# HC-05.net
KiCad netlist of a schematic drawn in Altium Designer
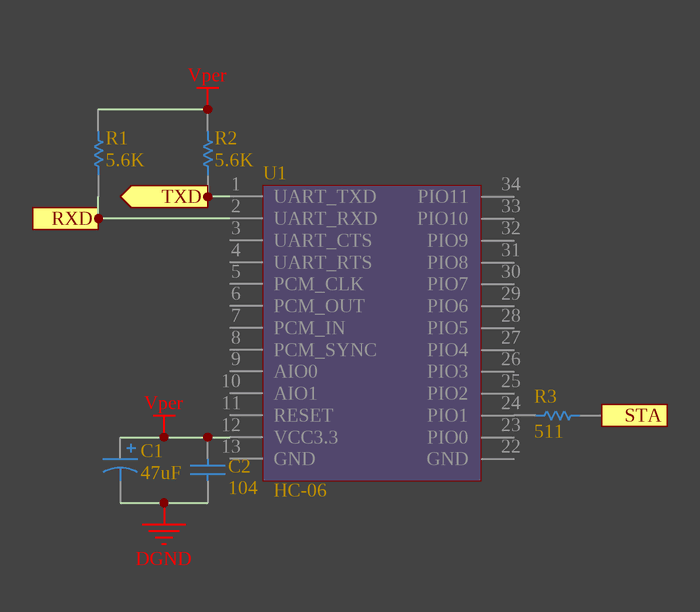
[diagram p0: HC-05.SchDoc]

(export (version "E")
  (design (tool "Eeschema 10.0.6"))
  (components
    (comp (ref "C1")
      (value "47uF")
      (footprint "贴片电解 6.3*5.4")
      (description "Polarized Capacitor (Axial)")
      (fields (field (name "PUBLISHER") "Altium Limited"))
      (libsource (lib "iMag") (part "电解电容"))
    )
    (comp (ref "C2")
      (value "104")
      (footprint "C0402")
      (description "Capacitor")
      (fields (field (name "PUBLISHER") "Altium Limited"))
      (libsource (lib "iMag") (part "电容"))
    )
    (comp (ref "R1")
      (value "5.6K")
      (footprint "R0402")
      (description "Resistor")
      (fields (field (name "PUBLISHER") "Altium Limited"))
      (libsource (lib "iMag") (part "电阻"))
    )
    (comp (ref "R2")
      (value "5.6K")
      (footprint "R0402")
      (description "Resistor")
      (fields (field (name "PUBLISHER") "Altium Limited"))
      (libsource (lib "iMag") (part "电阻"))
    )
    (comp (ref "R3")
      (value "511")
      (footprint "R0402")
      (description "Resistor")
      (fields (field (name "PUBLISHER") "Altium Limited"))
      (libsource (lib "iMag") (part "电阻"))
    )
    (comp (ref "U1")
      (value "HC-06")
      (footprint "HC-05")
      (description "蓝牙串口模块")
      (libsource (lib "iMag") (part "HC-05"))
    )
  )
  (nets
    (net (code "1") (name "/RXD") (class "Default")
      (node (ref "R1") (pin "1") (pinfunction "1_1") (pintype "passive"))
      (node (ref "U1") (pin "2") (pinfunction "UART_RXD_2") (pintype "passive"))
    )
    (net (code "2") (name "/STA") (class "Default")
      (node (ref "R3") (pin "1") (pinfunction "1_1") (pintype "passive"))
    )
    (net (code "3") (name "/TXD") (class "Default")
      (node (ref "R2") (pin "1") (pinfunction "1_1") (pintype "passive"))
      (node (ref "U1") (pin "1") (pinfunction "UART_TXD_1") (pintype "passive"))
    )
    (net (code "4") (name "DGND") (class "Default")
      (node (ref "C1") (pin "2") (pinfunction "2_2") (pintype "passive"))
      (node (ref "C2") (pin "1") (pinfunction "1_1") (pintype "passive"))
    )
    (net (code "5") (name "Net-(U1-PIO1)") (class "Default")
      (node (ref "R3") (pin "2") (pinfunction "2_2") (pintype "passive"))
      (node (ref "U1") (pin "24") (pinfunction "PIO1_24") (pintype "passive"))
    )
    (net (code "6") (name "Vper") (class "Default")
      (node (ref "C1") (pin "1") (pinfunction "1_1") (pintype "passive"))
      (node (ref "C2") (pin "2") (pinfunction "2_2") (pintype "passive"))
      (node (ref "R1") (pin "2") (pinfunction "2_2") (pintype "passive"))
      (node (ref "R2") (pin "2") (pinfunction "2_2") (pintype "passive"))
      (node (ref "U1") (pin "12") (pinfunction "VCC3.3_12") (pintype "passive"))
    )
    (net (code "7") (name "unconnected-(U1-AIO0-Pad9)") (class "Default")
      (node (ref "U1") (pin "9") (pinfunction "AIO0_9") (pintype "passive"))
    )
    (net (code "8") (name "unconnected-(U1-AIO1-Pad10)") (class "Default")
      (node (ref "U1") (pin "10") (pinfunction "AIO1_10") (pintype "passive"))
    )
    (net (code "9") (name "unconnected-(U1-GND-Pad13)") (class "Default")
      (node (ref "U1") (pin "13") (pinfunction "GND_13") (pintype "passive"))
    )
    (net (code "10") (name "unconnected-(U1-GND-Pad22)") (class "Default")
      (node (ref "U1") (pin "22") (pinfunction "GND_22") (pintype "passive"))
    )
    (net (code "11") (name "unconnected-(U1-PCM_CLK-Pad5)") (class "Default")
      (node (ref "U1") (pin "5") (pinfunction "PCM_CLK_5") (pintype "passive"))
    )
    (net (code "12") (name "unconnected-(U1-PCM_IN-Pad7)") (class "Default")
      (node (ref "U1") (pin "7") (pinfunction "PCM_IN_7") (pintype "passive"))
    )
    (net (code "13") (name "unconnected-(U1-PCM_OUT-Pad6)") (class "Default")
      (node (ref "U1") (pin "6") (pinfunction "PCM_OUT_6") (pintype "passive"))
    )
    (net (code "14") (name "unconnected-(U1-PCM_SYNC-Pad8)") (class "Default")
      (node (ref "U1") (pin "8") (pinfunction "PCM_SYNC_8") (pintype "passive"))
    )
    (net (code "15") (name "unconnected-(U1-PIO0-Pad23)") (class "Default")
      (node (ref "U1") (pin "23") (pinfunction "PIO0_23") (pintype "passive"))
    )
    (net (code "16") (name "unconnected-(U1-PIO2-Pad25)") (class "Default")
      (node (ref "U1") (pin "25") (pinfunction "PIO2_25") (pintype "passive"))
    )
    (net (code "17") (name "unconnected-(U1-PIO3-Pad26)") (class "Default")
      (node (ref "U1") (pin "26") (pinfunction "PIO3_26") (pintype "passive"))
    )
    (net (code "18") (name "unconnected-(U1-PIO4-Pad27)") (class "Default")
      (node (ref "U1") (pin "27") (pinfunction "PIO4_27") (pintype "passive"))
    )
    (net (code "19") (name "unconnected-(U1-PIO5-Pad28)") (class "Default")
      (node (ref "U1") (pin "28") (pinfunction "PIO5_28") (pintype "passive"))
    )
    (net (code "20") (name "unconnected-(U1-PIO6-Pad29)") (class "Default")
      (node (ref "U1") (pin "29") (pinfunction "PIO6_29") (pintype "passive"))
    )
    (net (code "21") (name "unconnected-(U1-PIO7-Pad30)") (class "Default")
      (node (ref "U1") (pin "30") (pinfunction "PIO7_30") (pintype "passive"))
    )
    (net (code "22") (name "unconnected-(U1-PIO8-Pad31)") (class "Default")
      (node (ref "U1") (pin "31") (pinfunction "PIO8_31") (pintype "passive"))
    )
    (net (code "23") (name "unconnected-(U1-PIO9-Pad32)") (class "Default")
      (node (ref "U1") (pin "32") (pinfunction "PIO9_32") (pintype "passive"))
    )
    (net (code "24") (name "unconnected-(U1-PIO10-Pad33)") (class "Default")
      (node (ref "U1") (pin "33") (pinfunction "PIO10_33") (pintype "passive"))
    )
    (net (code "25") (name "unconnected-(U1-PIO11-Pad34)") (class "Default")
      (node (ref "U1") (pin "34") (pinfunction "PIO11_34") (pintype "passive"))
    )
    (net (code "26") (name "unconnected-(U1-RESET-Pad11)") (class "Default")
      (node (ref "U1") (pin "11") (pinfunction "RESET_11") (pintype "passive"))
    )
    (net (code "27") (name "unconnected-(U1-UART_CTS-Pad3)") (class "Default")
      (node (ref "U1") (pin "3") (pinfunction "UART_CTS_3") (pintype "passive"))
    )
    (net (code "28") (name "unconnected-(U1-UART_RTS-Pad4)") (class "Default")
      (node (ref "U1") (pin "4") (pinfunction "UART_RTS_4") (pintype "passive"))
    )
  )
)
